# EPS_MCU.net
KiCad netlist of a schematic drawn in Altium Designer
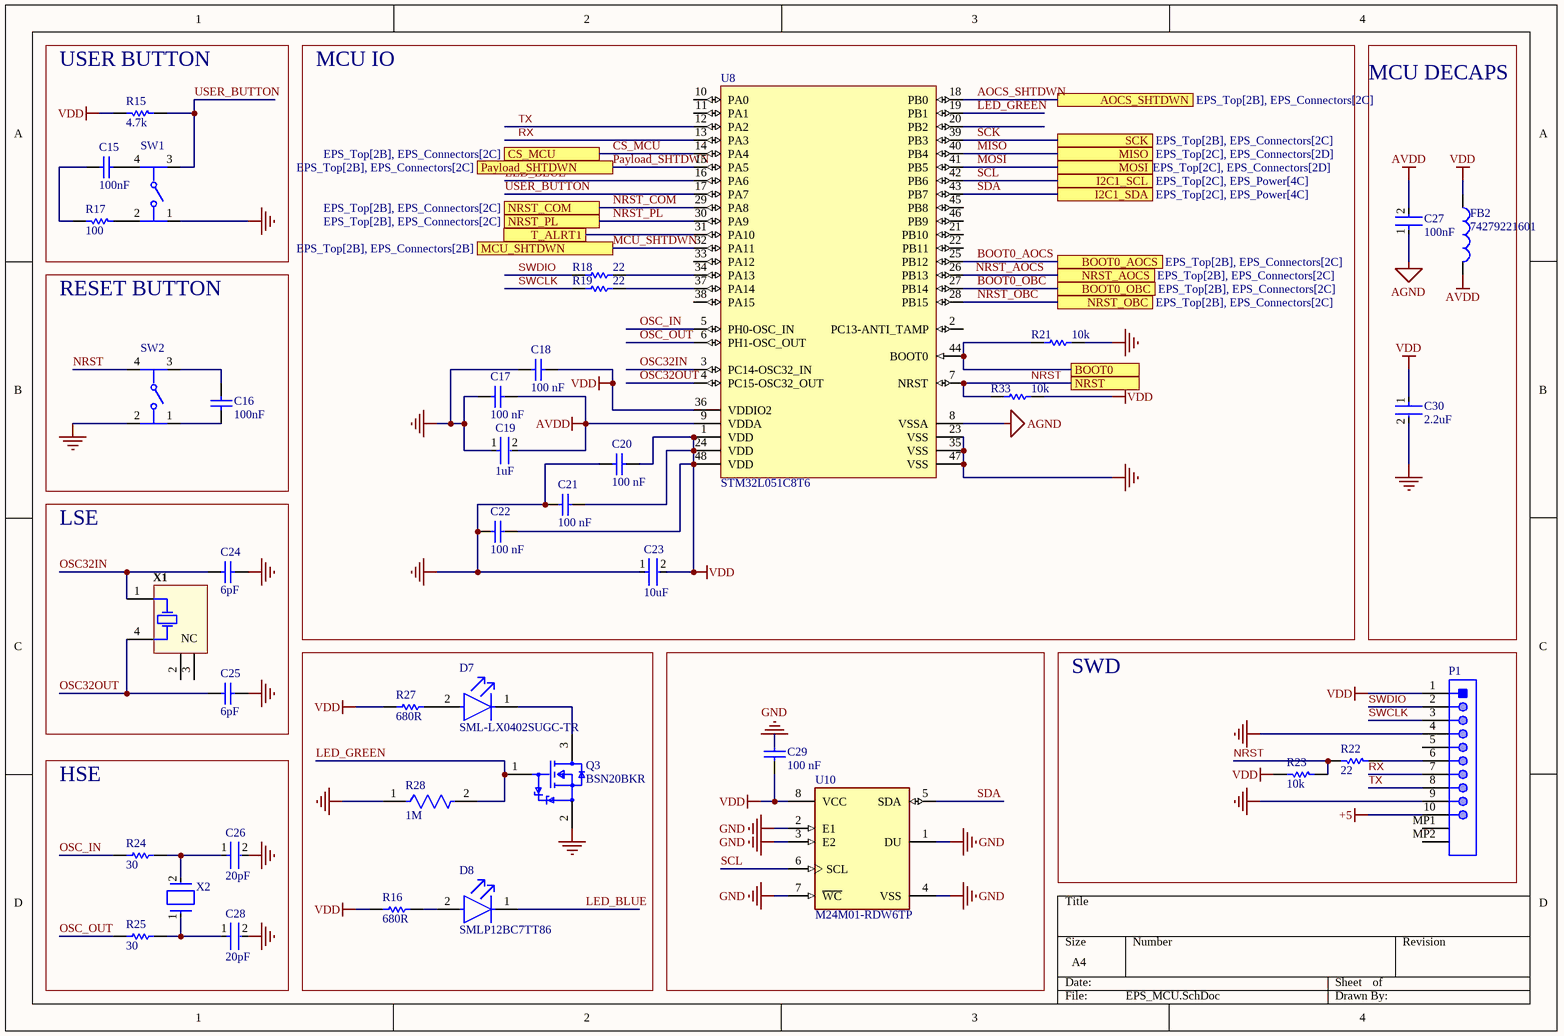
[diagram p0: EPS_MCU.SchDoc]

(export (version "E")
  (design (tool "Eeschema 10.0.6"))
  (components
    (comp (ref "C15")
      (value "100nF")
      (footprint "CAPC1050X55X23ML05T13")
      (description "Chip Capacitor, 100 nF, +/- 10%, 16 V, -55 to 125 degC, 0402 (1005 Metric), RoHS, Tape and Reel")
      (fields (field (name "MANUFACTURER") "Samsung Electro-Mechanics"))
      (libsource (lib "Altium Content Vault") (part "CAP-NP-2"))
    )
    (comp (ref "C16")
      (value "100nF")
      (footprint "CAPC1050X55X23ML05T13")
      (description "Chip Capacitor, 100 nF, +/- 10%, 16 V, -55 to 125 degC, 0402 (1005 Metric), RoHS, Tape and Reel")
      (fields (field (name "MANUFACTURER") "Samsung Electro-Mechanics"))
      (libsource (lib "Altium Content Vault") (part "CAP-NP-2"))
    )
    (comp (ref "C17")
      (value "100 nF")
      (footprint "CAPC1050X55X23ML05T13")
      (description "Chip Capacitor, 100 nF, +/- 10%, 16 V, -55 to 125 degC, 0402 (1005 Metric), RoHS, Tape and Reel")
      (fields (field (name "MANUFACTURER") "Samsung Electro-Mechanics"))
      (libsource (lib "Altium Content Vault") (part "CAP-NP-2"))
    )
    (comp (ref "C18")
      (value "100 nF")
      (footprint "CAPC1050X55X23ML05T13")
      (description "Chip Capacitor, 100 nF, +/- 10%, 16 V, -55 to 125 degC, 0402 (1005 Metric), RoHS, Tape and Reel")
      (fields (field (name "MANUFACTURER") "Samsung Electro-Mechanics"))
      (libsource (lib "Altium Content Vault") (part "CAP-NP-2"))
    )
    (comp (ref "C19")
      (value "1uF")
      (footprint "FP-CL10-IPC_A")
      (description "Cap Ceramic 1uF 16V X5R ±10% Pad SMD 0603 +85°C T/R")
      (fields (field (name "TOLERANCE") "10%") (field (name "VOLTAGE") "16V"))
      (libsource (lib "Altium Content Vault") (part "b4654b650e69147ec39a6b967a45e02"))
    )
    (comp (ref "C20")
      (value "100 nF")
      (footprint "CAPC1050X55X23ML05T13")
      (description "Chip Capacitor, 100 nF, +/- 10%, 16 V, -55 to 125 degC, 0402 (1005 Metric), RoHS, Tape and Reel")
      (fields (field (name "MANUFACTURER") "Samsung Electro-Mechanics"))
      (libsource (lib "Altium Content Vault") (part "CAP-NP-2"))
    )
    (comp (ref "C21")
      (value "100 nF")
      (footprint "CAPC1050X55X23ML05T13")
      (description "Chip Capacitor, 100 nF, +/- 10%, 16 V, -55 to 125 degC, 0402 (1005 Metric), RoHS, Tape and Reel")
      (fields (field (name "MANUFACTURER") "Samsung Electro-Mechanics"))
      (libsource (lib "Altium Content Vault") (part "CAP-NP-2"))
    )
    (comp (ref "C22")
      (value "100 nF")
      (footprint "CAPC1050X55X23ML05T13")
      (description "Chip Capacitor, 100 nF, +/- 10%, 16 V, -55 to 125 degC, 0402 (1005 Metric), RoHS, Tape and Reel")
      (fields (field (name "MANUFACTURER") "Samsung Electro-Mechanics"))
      (libsource (lib "Altium Content Vault") (part "CAP-NP-2"))
    )
    (comp (ref "C23")
      (value "10uF")
      (footprint "FP-CL21B106KOQNNNG-MFG")
      (description "CAP CER 10UF 16V X7R 0805")
      (fields (field (name "TOLERANCE") "10%") (field (name "MANUFACTURER PART NUMBER") "CL21B106KOQNNNG"))
      (libsource (lib "Altium Content Vault") (part "b4654b650e69147ec39a6b967a45e02"))
    )
    (comp (ref "C24")
      (value "6pF")
      (footprint "CAPC1005X55X25ML05T10")
      (fields (field (name "PART NUMBER") "GRM1555C1H6R0DA01D") (field (name "MANUFACTURER") "Murata"))
      (libsource (lib "Altium Content Vault") (part "CAP"))
    )
    (comp (ref "C25")
      (value "6pF")
      (footprint "CAPC1005X55X25ML05T10")
      (fields (field (name "PART NUMBER") "GRM1555C1H6R0DA01D") (field (name "MANUFACTURER") "Murata"))
      (libsource (lib "Altium Content Vault") (part "CAP"))
    )
    (comp (ref "C26")
      (value "20pF")
      (footprint "FP-GCM155-0_05-IPC_C")
      (description "Ceramic Capacitor for Automotive 20pF ±2% 50VDC C0G 0402 Paper T/R")
      (libsource (lib "Altium Content Vault") (part "02cd4be3c70576c341d710602a673aa"))
    )
    (comp (ref "C27")
      (value "100nF")
      (footprint "FP-CC0402-MFG")
      (description "CAP CER 0.1UF 16V X7R 0402")
      (fields (field (name "MANUFACTURER") "YAGEO") (field (name "TOLERANCE") "0.1"))
      (libsource (lib "Altium Content Vault") (part "11868f565c42a9108669ba33697ecf6"))
    )
    (comp (ref "C28")
      (value "20pF")
      (footprint "FP-GCM155-0_05-IPC_C")
      (description "Ceramic Capacitor for Automotive 20pF ±2% 50VDC C0G 0402 Paper T/R")
      (libsource (lib "Altium Content Vault") (part "02cd4be3c70576c341d710602a673aa"))
    )
    (comp (ref "C29")
      (value "100 nF")
      (footprint "CAPC1050X55X23ML05T13")
      (description "Chip Capacitor, 100 nF, +/- 10%, 16 V, -55 to 125 degC, 0402 (1005 Metric), RoHS, Tape and Reel")
      (fields (field (name "MANUFACTURER") "Samsung Electro-Mechanics"))
      (libsource (lib "Altium Content Vault") (part "CAP-NP-2"))
    )
    (comp (ref "C30")
      (value "2.2uF")
      (footprint "FP-CL10-IPC_A")
      (description "Cap Ceramic 2.2uF 16V X5R ±10% Pad SMD 0603 +85°C T/R")
      (fields (field (name "TOLERANCE") "10%") (field (name "VOLTAGE") "16V"))
      (libsource (lib "Altium Content Vault") (part "b4654b650e69147ec39a6b967a45e02"))
    )
    (comp (ref "D7")
      (value "SML-LX0402SUGC-TR")
      (footprint "FP-SML-LX0402SUGC-TR-MFG")
      (description "LED GREEN CLEAR SMD")
      (libsource (lib "Altium Content Vault") (part "8706943c75ba83719d021d2fdc84c58"))
    )
    (comp (ref "D8")
      (value "SMLP12BC7TT86")
      (footprint "FP-SML-P12-MFG")
      (description "LED BLUE CLEAR 1006 SMD")
      (fields
        (field (name "MANUFACTURER") "Rohm")
        (field (name "OCTOPART") "https://octopart.com/smlp12bc7tt86-rohm-9290887")
      )
      (libsource (lib "Altium Content Vault") (part "8706943c75ba83719d021d2fdc84c58"))
    )
    (comp (ref "FB2")
      (value "74279221601")
      (footprint "WE-MPSB_1206_L3.2W1.6H1.1")
      (fields (field (name "TOLERANCE") "25%"))
      (libsource (lib "Altium Content Vault") (part "Ferrite"))
    )
    (comp (ref "P1")
      (value "SM10B-SHLS-TF(LF)(SN)")
      (footprint "JST-SM10B-SHLS-TF_V")
      (description "Male Header, Pitch 1 mm, 1 x 10 Position, Height 1.8 mm, -25 to 85 degC")
      (fields (field (name "MANUFACTURER") "JST"))
      (libsource (lib "Altium Content Vault") (part "CN-1P-2M-R10"))
    )
    (comp (ref "Q3")
      (value "BSN20BKR")
      (footprint "FP-SOT23-IPC_C")
      (description "MOSFET N-CH 60V 265MA TO236AB")
      (libsource (lib "Altium Content Vault") (part "9f09aa45b414195f9603f7520b00189"))
    )
    (comp (ref "R15")
      (value "4.7k")
      (footprint "RESC1005X40X25LL05T05")
      (description "Chip Resistor, 4.7 KOhm, +/- 1%, 0.1 W, -55 to 155 degC, 0402 (1005 Metric), RoHS, Tape and Reel")
      (fields (field (name "TOLERANCE") "1%") (field (name "PARTNUMBER") "ERJ-2RKF4701X"))
      (libsource (lib "Altium Content Vault") (part "RES-2"))
    )
    (comp (ref "R16")
      (value "680R")
      (footprint "RESC1005X40X25ML05T05")
      (fields (field (name "MANUFACTURER") "Vishay Dale") (field (name "PART NUMBER") "CRCW0402680RFKED"))
      (libsource (lib "Altium Content Vault") (part "RES"))
    )
    (comp (ref "R17")
      (value "100")
      (footprint "RESC1608X55X30LL15T15")
      (fields (field (name "MANUFACTURER") "Panasonic") (field (name "PART NUMBER") "ERJ-3EKF1000V"))
      (libsource (lib "Altium Content Vault") (part "RES"))
    )
    (comp (ref "R18")
      (value "22")
      (footprint "RESC1608X55X25NL10T15")
      (description "Chip Resistor, 22 Ohm, +/- 1%, 0.1 W, -55 to 155 degC, 0603 (1608 Metric), RoHS, Tape and Reel")
      (libsource (lib "Altium Content Vault") (part "RES-2"))
    )
    (comp (ref "R19")
      (value "22")
      (footprint "RESC1608X55X25NL10T15")
      (description "Chip Resistor, 22 Ohm, +/- 1%, 0.1 W, -55 to 155 degC, 0603 (1608 Metric), RoHS, Tape and Reel")
      (libsource (lib "Altium Content Vault") (part "RES-2"))
    )
    (comp (ref "R21")
      (value "10k")
      (footprint "RESC1005X40X25LL05T10")
      (fields (field (name "PART NUMBER") "RC0402FR-0710KL") (field (name "MANUFACTURER") "Yageo / Phycomp"))
      (libsource (lib "Altium Content Vault") (part "RES"))
    )
    (comp (ref "R22")
      (value "22")
      (footprint "RESC1608X55X25NL10T15")
      (description "Chip Resistor, 22 Ohm, +/- 1%, 0.1 W, -55 to 155 degC, 0603 (1608 Metric), RoHS, Tape and Reel")
      (libsource (lib "Altium Content Vault") (part "RES-2"))
    )
    (comp (ref "R23")
      (value "10k")
      (footprint "RESC1005X40X25LL05T10")
      (fields (field (name "PART NUMBER") "RC0402FR-0710KL") (field (name "MANUFACTURER") "Yageo / Phycomp"))
      (libsource (lib "Altium Content Vault") (part "RES"))
    )
    (comp (ref "R24")
      (value "30")
      (footprint "RESC1609X50X30NL10T20")
      (fields (field (name "PART NUMBER") "CRCW060330R0FKEA") (field (name "MANUFACTURER") "Vishay Dale"))
      (libsource (lib "Altium Content Vault") (part "RES"))
    )
    (comp (ref "R25")
      (value "30")
      (footprint "RESC1609X50X30NL10T20")
      (fields (field (name "PART NUMBER") "CRCW060330R0FKEA") (field (name "MANUFACTURER") "Vishay Dale"))
      (libsource (lib "Altium Content Vault") (part "RES"))
    )
    (comp (ref "R27")
      (value "680R")
      (footprint "RESC1005X40X25ML05T05")
      (fields (field (name "MANUFACTURER") "Vishay Dale") (field (name "PART NUMBER") "CRCW0402680RFKED"))
      (libsource (lib "Altium Content Vault") (part "RES"))
    )
    (comp (ref "R28")
      (value "1M")
      (footprint "FP-MCR01-IPC_B")
      (description "Thick Film Chip Resistor, 0402, 1MΩ, 1%, 100ppm/°C, 0.063W, 50V")
      (fields (field (name "TOLERANCE") "1%"))
      (libsource (lib "Altium Content Vault") (part "1029c3af85768c4190bb7ad29bc67b5"))
    )
    (comp (ref "R33")
      (value "10k")
      (footprint "RESC1005X40X25LL05T10")
      (fields (field (name "PART NUMBER") "RC0402FR-0710KL") (field (name "MANUFACTURER") "Yageo / Phycomp"))
      (libsource (lib "Altium Content Vault") (part "RES"))
    )
    (comp (ref "SW1")
      (value "PTS810SJM250SMTRLFS")
      (footprint "FP-PTS810SJM250SMTRLFS-MFG")
      (description "SWITCH TACTILE SPST-NO 0.05A 16V")
      (libsource (lib "Altium Content Vault") (part "1adf0dd01260c80cf25a44bfd6b99ba"))
    )
    (comp (ref "SW2")
      (value "PTS810SJM250SMTRLFS")
      (footprint "FP-PTS810SJM250SMTRLFS-MFG")
      (description "SWITCH TACTILE SPST-NO 0.05A 16V")
      (libsource (lib "Altium Content Vault") (part "1adf0dd01260c80cf25a44bfd6b99ba"))
    )
    (comp (ref "U8")
      (value "STM32L051C8T6")
      (footprint "STM-LQFP48_L")
      (libsource (lib "Altium Content Vault") (part "STM-STM32L051-LQFP-48"))
    )
    (comp (ref "U10")
      (value "M24M01-RDW6TP")
      (footprint "FP-TSSOP8-TSSOP8AM-IPC_A")
      (description "IC EEPROM 1M I2C 1MHZ 8TSSOP")
      (fields
        (field (name "OCTOPART") "https://octopart.com/m24m01-rdw6tp-stmicroelectronics-55567287")
        (field (name "MANUFACTURER") "STMicroelectronics")
      )
      (libsource (lib "Altium Content Vault") (part "01e6ee3000284ae4c5c03a1c8b7b292"))
    )
    (comp (ref "X1")
      (value "ABS25-32.768KHZ-6-T")
      (footprint "ABRA-ABS25-4_V")
      (fields (field (name "TOLERANCE") "20PPM") (field (name "MANUFACTURER") "Abracon"))
      (libsource (lib "Altium Content Vault") (part "ABRA-XTAL_1-4-4"))
    )
    (comp (ref "X2")
      (value "ABM3-8.000MHZ-D2Y-T")
      (footprint "FP-ABM3-MFG")
      (description "Crystal 8MHz ±20ppm 18pF SMD-2 5mm x 3.2mm")
      (fields (field (name "TOLERANCE") "20ppm"))
      (libsource (lib "Altium Content Vault") (part "c23a69dc6c9e2f18f2079038eb95dd1"))
    )
  )
  (nets
    (net (code "1") (name "+5") (class "Default")
      (node (ref "P1") (pin "10") (pinfunction "10_10") (pintype "passive"))
    )
    (net (code "2") (name "/AOCS_SHTDWN") (class "Default")
      (node (ref "U8") (pin "18") (pinfunction "PB0_18") (pintype "bidirectional"))
    )
    (net (code "3") (name "/BOOT0") (class "Default")
      (node (ref "R21") (pin "2") (pinfunction "2_2") (pintype "passive"))
      (node (ref "U8") (pin "44") (pinfunction "BOOT0_44") (pintype "input"))
    )
    (net (code "4") (name "/BOOT0_AOCS") (class "Default")
      (node (ref "U8") (pin "25") (pinfunction "PB12_25") (pintype "bidirectional"))
    )
    (net (code "5") (name "/BOOT0_OBC") (class "Default")
      (node (ref "U8") (pin "27") (pinfunction "PB14_27") (pintype "bidirectional"))
    )
    (net (code "6") (name "/CS_MCU") (class "Default")
      (node (ref "U8") (pin "14") (pinfunction "PA4_14") (pintype "bidirectional"))
    )
    (net (code "7") (name "/LED_BLUE") (class "Default")
      (node (ref "D8") (pin "1") (pinfunction "C_1") (pintype "passive"))
      (node (ref "U8") (pin "16") (pinfunction "PA6_16") (pintype "bidirectional"))
    )
    (net (code "8") (name "/LED_GREEN") (class "Default")
      (node (ref "Q3") (pin "1") (pinfunction "G_1") (pintype "passive"))
      (node (ref "R28") (pin "2") (pinfunction "2_2") (pintype "passive"))
      (node (ref "U8") (pin "19") (pinfunction "PB1_19") (pintype "bidirectional"))
    )
    (net (code "9") (name "/MCU_SHTDWN") (class "Default")
      (node (ref "U8") (pin "32") (pinfunction "PA11_32") (pintype "bidirectional"))
    )
    (net (code "10") (name "/MISO") (class "Default")
      (node (ref "U8") (pin "40") (pinfunction "PB4_40") (pintype "bidirectional"))
    )
    (net (code "11") (name "/MOSI") (class "Default")
      (node (ref "U8") (pin "41") (pinfunction "PB5_41") (pintype "bidirectional"))
    )
    (net (code "12") (name "/NRST") (class "Default")
      (node (ref "R22") (pin "2") (pinfunction "2_2") (pintype "passive"))
      (node (ref "R23") (pin "2") (pinfunction "2_2") (pintype "passive"))
      (node (ref "R33") (pin "2") (pinfunction "2_2") (pintype "passive"))
      (node (ref "SW2") (pin "4") (pinfunction "4_4") (pintype "passive"))
      (node (ref "U8") (pin "7") (pinfunction "NRST_7") (pintype "bidirectional"))
    )
    (net (code "13") (name "/NRST_AOCS") (class "Default")
      (node (ref "U8") (pin "26") (pinfunction "PB13_26") (pintype "bidirectional"))
    )
    (net (code "14") (name "/NRST_COM") (class "Default")
      (node (ref "U8") (pin "29") (pinfunction "PA8_29") (pintype "bidirectional"))
    )
    (net (code "15") (name "/NRST_OBC") (class "Default")
      (node (ref "U8") (pin "28") (pinfunction "PB15_28") (pintype "bidirectional"))
    )
    (net (code "16") (name "/NRST_PL") (class "Default")
      (node (ref "U8") (pin "30") (pinfunction "PA9_30") (pintype "bidirectional"))
    )
    (net (code "17") (name "/OSC32IN") (class "Default")
      (node (ref "C24") (pin "1") (pinfunction "1_1") (pintype "passive"))
      (node (ref "U8") (pin "3") (pinfunction "PC14-OSC32_IN_3") (pintype "bidirectional"))
      (node (ref "X1") (pin "1") (pinfunction "X1_1") (pintype "passive"))
    )
    (net (code "18") (name "/OSC32OUT") (class "Default")
      (node (ref "C25") (pin "1") (pinfunction "1_1") (pintype "passive"))
      (node (ref "U8") (pin "4") (pinfunction "PC15-OSC32_OUT_4") (pintype "bidirectional"))
      (node (ref "X1") (pin "4") (pinfunction "X2_4") (pintype "passive"))
    )
    (net (code "19") (name "/OSC_IN") (class "Default")
      (node (ref "R24") (pin "1") (pinfunction "1_1") (pintype "passive"))
      (node (ref "U8") (pin "5") (pinfunction "PH0-OSC_IN_5") (pintype "bidirectional"))
    )
    (net (code "20") (name "/OSC_OUT") (class "Default")
      (node (ref "R25") (pin "1") (pinfunction "1_1") (pintype "passive"))
      (node (ref "U8") (pin "6") (pinfunction "PH1-OSC_OUT_6") (pintype "bidirectional"))
    )
    (net (code "21") (name "/Payload_SHTDWN") (class "Default")
      (node (ref "U8") (pin "15") (pinfunction "PA5_15") (pintype "bidirectional"))
    )
    (net (code "22") (name "/RX") (class "Default")
      (node (ref "P1") (pin "7") (pinfunction "7_7") (pintype "passive"))
      (node (ref "U8") (pin "13") (pinfunction "PA3_13") (pintype "bidirectional"))
    )
    (net (code "23") (name "/SCK") (class "Default")
      (node (ref "U8") (pin "39") (pinfunction "PB3_39") (pintype "bidirectional"))
    )
    (net (code "24") (name "/SCL") (class "Default")
      (node (ref "U10") (pin "6") (pinfunction "SCL_6") (pintype "input"))
      (node (ref "U8") (pin "42") (pinfunction "PB6_42") (pintype "bidirectional"))
    )
    (net (code "25") (name "/SDA") (class "Default")
      (node (ref "U10") (pin "5") (pinfunction "SDA_5") (pintype "bidirectional"))
      (node (ref "U8") (pin "43") (pinfunction "PB7_43") (pintype "bidirectional"))
    )
    (net (code "26") (name "/SWCLK") (class "Default")
      (node (ref "P1") (pin "3") (pinfunction "3_3") (pintype "passive"))
      (node (ref "R19") (pin "1") (pinfunction "1_1") (pintype "passive"))
    )
    (net (code "27") (name "/SWDIO") (class "Default")
      (node (ref "P1") (pin "2") (pinfunction "2_2") (pintype "passive"))
      (node (ref "R18") (pin "1") (pinfunction "1_1") (pintype "passive"))
    )
    (net (code "28") (name "/TX") (class "Default")
      (node (ref "P1") (pin "8") (pinfunction "8_8") (pintype "passive"))
      (node (ref "U8") (pin "12") (pinfunction "PA2_12") (pintype "bidirectional"))
    )
    (net (code "29") (name "/T_ALRT1") (class "Default")
      (node (ref "U8") (pin "31") (pinfunction "PA10_31") (pintype "bidirectional"))
    )
    (net (code "30") (name "/USER_BUTTON") (class "Default")
      (node (ref "R15") (pin "1") (pinfunction "1_1") (pintype "passive"))
      (node (ref "SW1") (pin "3") (pinfunction "3_3") (pintype "passive"))
      (node (ref "U8") (pin "17") (pinfunction "PA7_17") (pintype "bidirectional"))
    )
    (net (code "31") (name "AGND") (class "Default")
      (node (ref "C27") (pin "1") (pinfunction "1_1") (pintype "passive"))
      (node (ref "U8") (pin "8") (pinfunction "VSSA_8") (pintype "power_in"))
    )
    (net (code "32") (name "AVDD") (class "Default")
      (node (ref "C17") (pin "2") (pinfunction "2_2") (pintype "passive"))
      (node (ref "C19") (pin "2") (pinfunction "2_2") (pintype "passive"))
      (node (ref "C27") (pin "2") (pinfunction "2_2") (pintype "passive"))
      (node (ref "FB2") (pin "2") (pinfunction "2_2") (pintype "passive"))
      (node (ref "U8") (pin "9") (pinfunction "VDDA_9") (pintype "power_in"))
    )
    (net (code "33") (name "GND") (class "Default")
      (node (ref "C17") (pin "1") (pinfunction "1_1") (pintype "passive"))
      (node (ref "C18") (pin "1") (pinfunction "1_1") (pintype "passive"))
      (node (ref "C19") (pin "1") (pinfunction "1_1") (pintype "passive"))
      (node (ref "C20") (pin "1") (pinfunction "1_1") (pintype "passive"))
      (node (ref "C21") (pin "1") (pinfunction "1_1") (pintype "passive"))
      (node (ref "C22") (pin "1") (pinfunction "1_1") (pintype "passive"))
      (node (ref "C23") (pin "1") (pinfunction "1_1") (pintype "passive"))
      (node (ref "C24") (pin "2") (pinfunction "2_2") (pintype "passive"))
      (node (ref "C25") (pin "2") (pinfunction "2_2") (pintype "passive"))
      (node (ref "C26") (pin "2") (pinfunction "2_2") (pintype "passive"))
      (node (ref "C28") (pin "2") (pinfunction "2_2") (pintype "passive"))
      (node (ref "C29") (pin "2") (pinfunction "2_2") (pintype "passive"))
      (node (ref "C30") (pin "2") (pinfunction "2_2") (pintype "passive"))
      (node (ref "P1") (pin "4") (pinfunction "4_4") (pintype "passive"))
      (node (ref "P1") (pin "9") (pinfunction "9_9") (pintype "passive"))
      (node (ref "Q3") (pin "2") (pinfunction "S_2") (pintype "passive"))
      (node (ref "R21") (pin "1") (pinfunction "1_1") (pintype "passive"))
      (node (ref "R28") (pin "1") (pinfunction "1_1") (pintype "passive"))
      (node (ref "SW1") (pin "1") (pinfunction "1_1") (pintype "passive"))
      (node (ref "SW2") (pin "2") (pinfunction "2_2") (pintype "passive"))
      (node (ref "U10") (pin "1") (pinfunction "DU_1") (pintype "passive"))
      (node (ref "U10") (pin "2") (pinfunction "E1_2") (pintype "input"))
      (node (ref "U10") (pin "3") (pinfunction "E2_3") (pintype "input"))
      (node (ref "U10") (pin "4") (pinfunction "VSS_4") (pintype "power_in"))
      (node (ref "U10") (pin "7") (pinfunction "~{WC}_7") (pintype "input"))
      (node (ref "U8") (pin "23") (pinfunction "VSS_23") (pintype "power_in"))
      (node (ref "U8") (pin "35") (pinfunction "VSS_35") (pintype "power_in"))
      (node (ref "U8") (pin "47") (pinfunction "VSS_47") (pintype "power_in"))
    )
    (net (code "34") (name "Net-(C15-Pad1)") (class "Default")
      (node (ref "C15") (pin "1") (pinfunction "1_1") (pintype "passive"))
      (node (ref "SW1") (pin "4") (pinfunction "4_4") (pintype "passive"))
    )
    (net (code "35") (name "Net-(C15-Pad2)") (class "Default")
      (node (ref "C15") (pin "2") (pinfunction "2_2") (pintype "passive"))
      (node (ref "R17") (pin "2") (pinfunction "2_2") (pintype "passive"))
    )
    (net (code "36") (name "Net-(C16-Pad1)") (class "Default")
      (node (ref "C16") (pin "1") (pinfunction "1_1") (pintype "passive"))
      (node (ref "SW2") (pin "1") (pinfunction "1_1") (pintype "passive"))
    )
    (net (code "37") (name "Net-(C16-Pad2)") (class "Default")
      (node (ref "C16") (pin "2") (pinfunction "2_2") (pintype "passive"))
      (node (ref "SW2") (pin "3") (pinfunction "3_3") (pintype "passive"))
    )
    (net (code "38") (name "Net-(C26-Pad1)") (class "Default")
      (node (ref "C26") (pin "1") (pinfunction "1_1") (pintype "passive"))
      (node (ref "R24") (pin "2") (pinfunction "2_2") (pintype "passive"))
      (node (ref "X2") (pin "2") (pinfunction "2_2") (pintype "passive"))
    )
    (net (code "39") (name "Net-(C28-Pad1)") (class "Default")
      (node (ref "C28") (pin "1") (pinfunction "1_1") (pintype "passive"))
      (node (ref "R25") (pin "2") (pinfunction "2_2") (pintype "passive"))
      (node (ref "X2") (pin "1") (pinfunction "1_1") (pintype "passive"))
    )
    (net (code "40") (name "Net-(D7-A)") (class "Default")
      (node (ref "D7") (pin "2") (pinfunction "A_2") (pintype "passive"))
      (node (ref "R27") (pin "2") (pinfunction "2_2") (pintype "passive"))
    )
    (net (code "41") (name "Net-(D7-C)") (class "Default")
      (node (ref "D7") (pin "1") (pinfunction "C_1") (pintype "passive"))
      (node (ref "Q3") (pin "3") (pinfunction "D_3") (pintype "passive"))
    )
    (net (code "42") (name "Net-(D8-A)") (class "Default")
      (node (ref "D8") (pin "2") (pinfunction "A_2") (pintype "passive"))
      (node (ref "R16") (pin "2") (pinfunction "2_2") (pintype "passive"))
    )
    (net (code "43") (name "Net-(P1-Pad6)") (class "Default")
      (node (ref "P1") (pin "6") (pinfunction "6_6") (pintype "passive"))
      (node (ref "R22") (pin "1") (pinfunction "1_1") (pintype "passive"))
    )
    (net (code "44") (name "Net-(R17-Pad1)") (class "Default")
      (node (ref "R17") (pin "1") (pinfunction "1_1") (pintype "passive"))
      (node (ref "SW1") (pin "2") (pinfunction "2_2") (pintype "passive"))
    )
    (net (code "45") (name "Net-(U8-PA13)") (class "Default")
      (node (ref "R18") (pin "2") (pinfunction "2_2") (pintype "passive"))
      (node (ref "U8") (pin "34") (pinfunction "PA13_34") (pintype "bidirectional"))
    )
    (net (code "46") (name "Net-(U8-PA14)") (class "Default")
      (node (ref "R19") (pin "2") (pinfunction "2_2") (pintype "passive"))
      (node (ref "U8") (pin "37") (pinfunction "PA14_37") (pintype "bidirectional"))
    )
    (net (code "47") (name "VDD") (class "Default")
      (node (ref "C18") (pin "2") (pinfunction "2_2") (pintype "passive"))
      (node (ref "C20") (pin "2") (pinfunction "2_2") (pintype "passive"))
      (node (ref "C21") (pin "2") (pinfunction "2_2") (pintype "passive"))
      (node (ref "C22") (pin "2") (pinfunction "2_2") (pintype "passive"))
      (node (ref "C23") (pin "2") (pinfunction "2_2") (pintype "passive"))
      (node (ref "C29") (pin "1") (pinfunction "1_1") (pintype "passive"))
      (node (ref "C30") (pin "1") (pinfunction "1_1") (pintype "passive"))
      (node (ref "FB2") (pin "1") (pinfunction "1_1") (pintype "passive"))
      (node (ref "P1") (pin "1") (pinfunction "1_1") (pintype "passive"))
      (node (ref "R15") (pin "2") (pinfunction "2_2") (pintype "passive"))
      (node (ref "R16") (pin "1") (pinfunction "1_1") (pintype "passive"))
      (node (ref "R23") (pin "1") (pinfunction "1_1") (pintype "passive"))
      (node (ref "R27") (pin "1") (pinfunction "1_1") (pintype "passive"))
      (node (ref "R33") (pin "1") (pinfunction "1_1") (pintype "passive"))
      (node (ref "U10") (pin "8") (pinfunction "VCC_8") (pintype "power_in"))
      (node (ref "U8") (pin "1") (pinfunction "VDD_1") (pintype "power_in"))
      (node (ref "U8") (pin "24") (pinfunction "VDD_24") (pintype "power_in"))
      (node (ref "U8") (pin "36") (pinfunction "VDDIO2_36") (pintype "power_in"))
      (node (ref "U8") (pin "48") (pinfunction "VDD_48") (pintype "power_in"))
    )
    (net (code "48") (name "unconnected-(P1-Pad5)") (class "Default")
      (node (ref "P1") (pin "5") (pinfunction "5_5") (pintype "passive"))
    )
    (net (code "49") (name "unconnected-(P1-PadMP1)") (class "Default")
      (node (ref "P1") (pin "MP1") (pinfunction "MP1_MP1") (pintype "passive"))
    )
    (net (code "50") (name "unconnected-(P1-PadMP2)") (class "Default")
      (node (ref "P1") (pin "MP2") (pinfunction "MP2_MP2") (pintype "passive"))
    )
    (net (code "51") (name "unconnected-(U8-PA0-Pad10)") (class "Default")
      (node (ref "U8") (pin "10") (pinfunction "PA0_10") (pintype "bidirectional"))
    )
    (net (code "52") (name "unconnected-(U8-PA1-Pad11)") (class "Default")
      (node (ref "U8") (pin "11") (pinfunction "PA1_11") (pintype "bidirectional"))
    )
    (net (code "53") (name "unconnected-(U8-PA12-Pad33)") (class "Default")
      (node (ref "U8") (pin "33") (pinfunction "PA12_33") (pintype "bidirectional"))
    )
    (net (code "54") (name "unconnected-(U8-PA15-Pad38)") (class "Default")
      (node (ref "U8") (pin "38") (pinfunction "PA15_38") (pintype "bidirectional"))
    )
    (net (code "55") (name "unconnected-(U8-PB2-Pad20)") (class "Default")
      (node (ref "U8") (pin "20") (pinfunction "PB2_20") (pintype "bidirectional"))
    )
    (net (code "56") (name "unconnected-(U8-PB8-Pad45)") (class "Default")
      (node (ref "U8") (pin "45") (pinfunction "PB8_45") (pintype "bidirectional"))
    )
    (net (code "57") (name "unconnected-(U8-PB9-Pad46)") (class "Default")
      (node (ref "U8") (pin "46") (pinfunction "PB9_46") (pintype "bidirectional"))
    )
    (net (code "58") (name "unconnected-(U8-PB10-Pad21)") (class "Default")
      (node (ref "U8") (pin "21") (pinfunction "PB10_21") (pintype "bidirectional"))
    )
    (net (code "59") (name "unconnected-(U8-PB11-Pad22)") (class "Default")
      (node (ref "U8") (pin "22") (pinfunction "PB11_22") (pintype "bidirectional"))
    )
    (net (code "60") (name "unconnected-(U8-PC13-ANTI_TAMP-Pad2)") (class "Default")
      (node (ref "U8") (pin "2") (pinfunction "PC13-ANTI_TAMP_2") (pintype "bidirectional"))
    )
    (net (code "61") (name "unconnected-(X1-NC-Pad2)") (class "Default")
      (node (ref "X1") (pin "2") (pinfunction "NC_2") (pintype "passive"))
    )
    (net (code "62") (name "unconnected-(X1-NC-Pad3)") (class "Default")
      (node (ref "X1") (pin "3") (pinfunction "NC_3") (pintype "passive"))
    )
  )
)
